# hall_sensor.net
KiCad netlist of a schematic drawn in EAGLE
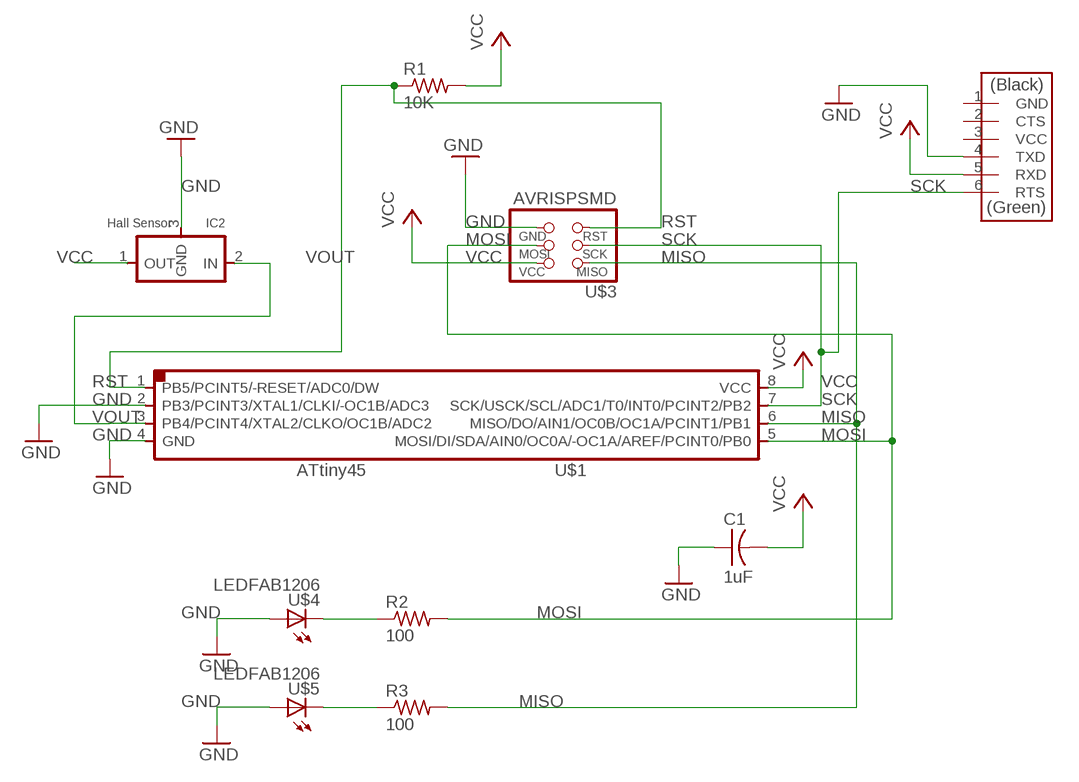
[diagram p0: schematic, sheet 1]

(export (version "E")
  (design (tool "Eeschema 10.0.6"))
  (components
    (comp (ref "C1")
      (value "1uF")
      (footprint "eagle-import:C1206FAB")
      (libsource (lib "eagle-import") (part "CAP-US1206FAB"))
    )
    (comp (ref "IC2")
      (value "Hall Sensor")
      (footprint "eagle-import:SOT23")
      (libsource (lib "eagle-import") (part "REGULATORSOT23"))
    )
    (comp (ref "R1")
      (value "10K")
      (footprint "eagle-import:R1206FAB")
      (libsource (lib "eagle-import") (part "RES-US1206FAB"))
    )
    (comp (ref "R2")
      (value "100")
      (footprint "eagle-import:R1206FAB")
      (libsource (lib "eagle-import") (part "RES-US1206FAB"))
    )
    (comp (ref "R3")
      (value "100")
      (footprint "eagle-import:R1206FAB")
      (libsource (lib "eagle-import") (part "RES-US1206FAB"))
    )
    (comp (ref "U$1")
      (value "ATTINY45SI")
      (footprint "eagle-import:SOIC8")
      (libsource (lib "eagle-import") (part "ATTINY45SI"))
    )
    (comp (ref "U$2")
      (value "FTDI-SMD-HEADER")
      (footprint "eagle-import:1X06SMD")
      (libsource (lib "eagle-import") (part "FTDI-SMD-HEADER"))
    )
    (comp (ref "U$3")
      (value "AVRISPSMD")
      (footprint "eagle-import:2X03SMD")
      (libsource (lib "eagle-import") (part "AVRISPSMD"))
    )
    (comp (ref "U$4")
      (value "LEDFAB1206")
      (footprint "eagle-import:LED1206FAB")
      (libsource (lib "eagle-import") (part "LEDFAB1206"))
    )
    (comp (ref "U$5")
      (value "LEDFAB1206")
      (footprint "eagle-import:LED1206FAB")
      (libsource (lib "eagle-import") (part "LEDFAB1206"))
    )
  )
  (nets
    (net (code "1") (name "/MISO") (class "Default")
      (node (ref "R3") (pin "2") (pinfunction "2_2") (pintype "passive"))
      (node (ref "U$1") (pin "6") (pinfunction "MISO/DO/AIN1/OC0B/OC1A/PCINT1/PB1_6") (pintype "bidirectional"))
      (node (ref "U$3") (pin "1") (pinfunction "MISO_1") (pintype "passive"))
    )
    (net (code "2") (name "/MOSI") (class "Default")
      (node (ref "R2") (pin "2") (pinfunction "2_2") (pintype "passive"))
      (node (ref "U$1") (pin "5") (pinfunction "MOSI/DI/SDA/AIN0/OC0A/-OC1A/AREF/PCINT0/PB0_5") (pintype "bidirectional"))
      (node (ref "U$3") (pin "4") (pinfunction "MOSI_4") (pintype "passive"))
    )
    (net (code "3") (name "/RST") (class "Default")
      (node (ref "R1") (pin "1") (pinfunction "1_1") (pintype "passive"))
      (node (ref "U$1") (pin "1") (pinfunction "PB5/PCINT5/-RESET/ADC0/DW_1") (pintype "bidirectional"))
      (node (ref "U$3") (pin "5") (pinfunction "RST_5") (pintype "passive"))
    )
    (net (code "4") (name "/SCK") (class "Default")
      (node (ref "U$1") (pin "7") (pinfunction "SCK/USCK/SCL/ADC1/T0/INT0/PCINT2/PB2_7") (pintype "bidirectional"))
      (node (ref "U$2") (pin "6") (pinfunction "RTS_6") (pintype "bidirectional"))
      (node (ref "U$3") (pin "3") (pinfunction "SCK_3") (pintype "passive"))
    )
    (net (code "5") (name "/VOUT") (class "Default")
      (node (ref "IC2") (pin "2") (pinfunction "IN_2") (pintype "bidirectional"))
      (node (ref "U$1") (pin "3") (pinfunction "PB4/PCINT4/XTAL2/CLKO/OC1B/ADC2_3") (pintype "bidirectional"))
    )
    (net (code "6") (name "GND") (class "Default")
      (node (ref "C1") (pin "1") (pinfunction "1_1") (pintype "passive"))
      (node (ref "IC2") (pin "3") (pinfunction "GND_3") (pintype "bidirectional"))
      (node (ref "U$1") (pin "2") (pinfunction "PB3/PCINT3/XTAL1/CLKI/-OC1B/ADC3_2") (pintype "bidirectional"))
      (node (ref "U$1") (pin "4") (pinfunction "GND_4") (pintype "bidirectional"))
      (node (ref "U$2") (pin "4") (pinfunction "TXD_4") (pintype "bidirectional"))
      (node (ref "U$3") (pin "6") (pinfunction "GND_6") (pintype "passive"))
      (node (ref "U$4") (pin "1") (pinfunction "A_1") (pintype "passive"))
      (node (ref "U$5") (pin "1") (pinfunction "A_1") (pintype "passive"))
    )
    (net (code "7") (name "Net-(U$4-C)") (class "Default")
      (node (ref "R2") (pin "1") (pinfunction "1_1") (pintype "passive"))
      (node (ref "U$4") (pin "2") (pinfunction "C_2") (pintype "passive"))
    )
    (net (code "8") (name "Net-(U$5-C)") (class "Default")
      (node (ref "R3") (pin "1") (pinfunction "1_1") (pintype "passive"))
      (node (ref "U$5") (pin "2") (pinfunction "C_2") (pintype "passive"))
    )
    (net (code "9") (name "VCC") (class "Default")
      (node (ref "C1") (pin "2") (pinfunction "2_2") (pintype "passive"))
      (node (ref "IC2") (pin "1") (pinfunction "OUT_1") (pintype "bidirectional"))
      (node (ref "R1") (pin "2") (pinfunction "2_2") (pintype "passive"))
      (node (ref "U$1") (pin "8") (pinfunction "VCC_8") (pintype "bidirectional"))
      (node (ref "U$2") (pin "5") (pinfunction "RXD_5") (pintype "bidirectional"))
      (node (ref "U$3") (pin "2") (pinfunction "VCC_2") (pintype "passive"))
    )
    (net (code "10") (name "unconnected-(U$2-CTS-Pad2)") (class "Default")
      (node (ref "U$2") (pin "2") (pinfunction "CTS_2") (pintype "bidirectional"))
    )
    (net (code "11") (name "unconnected-(U$2-GND-Pad1)") (class "Default")
      (node (ref "U$2") (pin "1") (pinfunction "GND_1") (pintype "bidirectional"))
    )
    (net (code "12") (name "unconnected-(U$2-VCC-Pad3)") (class "Default")
      (node (ref "U$2") (pin "3") (pinfunction "VCC_3") (pintype "bidirectional"))
    )
  )
)
